# QSFP.net
KiCad netlist of a schematic drawn in Altium Designer
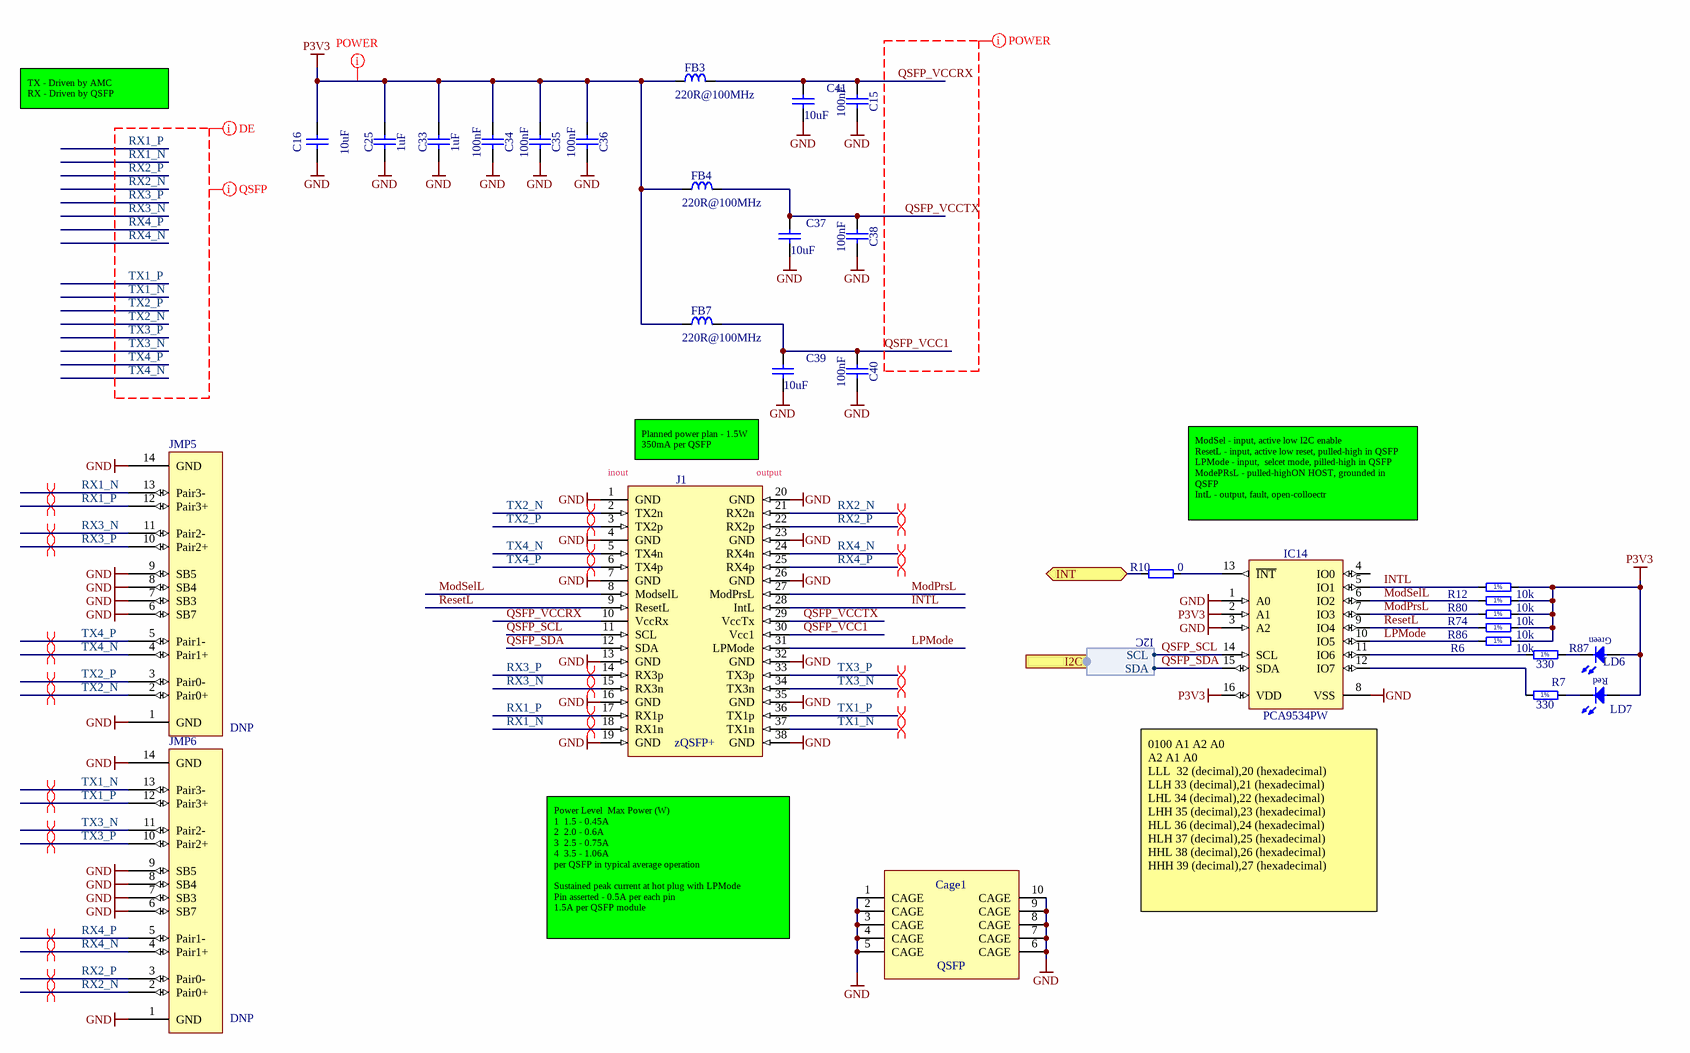
[diagram p0: QSFP.SchDoc]

(export (version "E")
  (design (tool "Eeschema 10.0.6"))
  (components
    (comp (ref "C15")
      (value "100nF")
      (footprint "CAPC0603X33N")
      (description "Non-polarised capacitor")
      (fields
        (field (name "PART NUMBER") "CC0201_100NF_6.3V_10%_X5R")
        (field (name "VOLTAGE") "6.3V")
        (field (name "AUTHOR") "CERN DEM JLC")
      )
      (libsource (lib "Capacitors") (part "Capacitor - non polarized"))
    )
    (comp (ref "C16")
      (value "10uF")
      (footprint "CAPC2012X135N")
      (description "Non-polarised capacitor")
      (fields
        (field (name "PART NUMBER") "CC0805_10UF_10V_10%_X7R")
        (field (name "VOLTAGE") "10V")
        (field (name "AUTHOR") "CERN DEM JLC")
      )
      (libsource (lib "Capacitors") (part "Capacitor - non polarized"))
    )
    (comp (ref "C25")
      (value "1uF")
      (footprint "CAPC1608X87N")
      (description "Non-polarised capacitor")
      (fields
        (field (name "PART NUMBER") "CC0603_1UF_25V_10%_X7R")
        (field (name "VOLTAGE") "25V")
        (field (name "AUTHOR") "CERN DEM JLC")
      )
      (libsource (lib "Capacitors") (part "Capacitor - non polarized"))
    )
    (comp (ref "C33")
      (value "1uF")
      (footprint "CAPC1608X87N")
      (description "Non-polarised capacitor")
      (fields
        (field (name "PART NUMBER") "CC0603_1UF_25V_10%_X7R")
        (field (name "VOLTAGE") "25V")
        (field (name "AUTHOR") "CERN DEM JLC")
      )
      (libsource (lib "Capacitors") (part "Capacitor - non polarized"))
    )
    (comp (ref "C34")
      (value "100nF")
      (footprint "CAPC0603X33N")
      (description "Non-polarised capacitor")
      (fields
        (field (name "PART NUMBER") "CC0201_100NF_6.3V_10%_X5R")
        (field (name "VOLTAGE") "6.3V")
        (field (name "AUTHOR") "CERN DEM JLC")
      )
      (libsource (lib "Capacitors") (part "Capacitor - non polarized"))
    )
    (comp (ref "C35")
      (value "100nF")
      (footprint "CAPC0603X33N")
      (description "Non-polarised capacitor")
      (fields
        (field (name "PART NUMBER") "CC0201_100NF_6.3V_10%_X5R")
        (field (name "VOLTAGE") "6.3V")
        (field (name "AUTHOR") "CERN DEM JLC")
      )
      (libsource (lib "Capacitors") (part "Capacitor - non polarized"))
    )
    (comp (ref "C36")
      (value "100nF")
      (footprint "CAPC0603X33N")
      (description "Non-polarised capacitor")
      (fields
        (field (name "PART NUMBER") "CC0201_100NF_6.3V_10%_X5R")
        (field (name "VOLTAGE") "6.3V")
        (field (name "AUTHOR") "CERN DEM JLC")
      )
      (libsource (lib "Capacitors") (part "Capacitor - non polarized"))
    )
    (comp (ref "C37")
      (value "10uF")
      (footprint "CAPC2012X135N")
      (description "Non-polarised capacitor")
      (fields
        (field (name "PART NUMBER") "CC0805_10UF_10V_10%_X7R")
        (field (name "VOLTAGE") "10V")
        (field (name "AUTHOR") "CERN DEM JLC")
      )
      (libsource (lib "Capacitors") (part "Capacitor - non polarized"))
    )
    (comp (ref "C38")
      (value "100nF")
      (footprint "CAPC0603X33N")
      (description "Non-polarised capacitor")
      (fields
        (field (name "PART NUMBER") "CC0201_100NF_6.3V_10%_X5R")
        (field (name "VOLTAGE") "6.3V")
        (field (name "AUTHOR") "CERN DEM JLC")
      )
      (libsource (lib "Capacitors") (part "Capacitor - non polarized"))
    )
    (comp (ref "C39")
      (value "10uF")
      (footprint "CAPC2012X135N")
      (description "Non-polarised capacitor")
      (fields
        (field (name "PART NUMBER") "CC0805_10UF_10V_10%_X7R")
        (field (name "VOLTAGE") "10V")
        (field (name "AUTHOR") "CERN DEM JLC")
      )
      (libsource (lib "Capacitors") (part "Capacitor - non polarized"))
    )
    (comp (ref "C40")
      (value "100nF")
      (footprint "CAPC0603X33N")
      (description "Non-polarised capacitor")
      (fields
        (field (name "PART NUMBER") "CC0201_100NF_6.3V_10%_X5R")
        (field (name "VOLTAGE") "6.3V")
        (field (name "AUTHOR") "CERN DEM JLC")
      )
      (libsource (lib "Capacitors") (part "Capacitor - non polarized"))
    )
    (comp (ref "C41")
      (value "10uF")
      (footprint "CAPC2012X135N")
      (description "Non-polarised capacitor")
      (fields
        (field (name "PART NUMBER") "CC0805_10UF_10V_10%_X7R")
        (field (name "VOLTAGE") "10V")
        (field (name "AUTHOR") "CERN DEM JLC")
      )
      (libsource (lib "Capacitors") (part "Capacitor - non polarized"))
    )
    (comp (ref "Cage1")
      (value "QSFP")
      (footprint "TYCO_2170703-7")
      (description "QSFP 1x1 Cage (10Pins)")
      (fields
        (field (name "PART NUMBER") "TYCO_2170703-7")
        (field (name "MANUFACTURER") "TYCO ELECTRONICS")
        (field (name "AUTHOR") "CERN DEM HF")
      )
      (libsource (lib "Connectors") (part "QSFP 1x1 Cage (10Pins)"))
    )
    (comp (ref "FB3")
      (value "220R@100MHz")
      (footprint "INDC2012X105N")
      (description "Inductor")
      (fields
        (field (name "PART NUMBER") "IND0805_MURATA_BLM21PG221SN1D")
        (field (name "POWER") "2A")
        (field (name "AUTHOR") "CERN DEM JLC")
      )
      (libsource (lib "Inductors & Transformers") (part "Inductor"))
    )
    (comp (ref "FB4")
      (value "220R@100MHz")
      (footprint "INDC2012X105N")
      (description "Inductor")
      (fields
        (field (name "PART NUMBER") "IND0805_MURATA_BLM21PG221SN1D")
        (field (name "POWER") "2A")
        (field (name "AUTHOR") "CERN DEM JLC")
      )
      (libsource (lib "Inductors & Transformers") (part "Inductor"))
    )
    (comp (ref "FB7")
      (value "220R@100MHz")
      (footprint "INDC2012X105N")
      (description "Inductor")
      (fields
        (field (name "PART NUMBER") "IND0805_MURATA_BLM21PG221SN1D")
        (field (name "POWER") "2A")
        (field (name "AUTHOR") "CERN DEM JLC")
      )
      (libsource (lib "Inductors & Transformers") (part "Inductor"))
    )
    (comp (ref "IC14")
      (value "PCA9534PW")
      (footprint "SOP65P640X110-16N")
      (description "8-Bit I2C-Bus and SMBus Low Power I/O Port with Interrupt")
      (fields (field (name "MANUFACTURER") "ANALOG DEVICES") (field (name "AUTHOR") "CERN DEM JLC"))
      (libsource (lib "ICs And Semiconductors") (part "PCA9534PW"))
    )
    (comp (ref "J1")
      (value "zQSFP+")
      (footprint "TYCO_1551920-2")
      (description "38Position QSFP Connector  (Quad Small Form-factor Pluggable)")
      (fields
        (field (name "PART NUMBER") "TYCO_1551920-2")
        (field (name "MANUFACTURER") "TYCO ELECTRONICS")
        (field (name "AUTHOR") "CERN DEM JLC")
      )
      (libsource (lib "Connectors") (part "QSFP+x1"))
    )
    (comp (ref "JMP5")
      (value "DNP")
      (footprint "3M_Twinax_SL8801/12-10DA5-00")
      (libsource (lib "LIBRARY_SCH") (part "DNP"))
    )
    (comp (ref "JMP6")
      (value "DNP")
      (footprint "3M_Twinax_SL8801/12-10DA5-00")
      (libsource (lib "LIBRARY_SCH") (part "DNP"))
    )
    (comp (ref "LD6")
      (value "LED_AVAGO_HSME-C120")
      (footprint "LED_AVAGO_HSME-C120")
      (description "LED Green 1C 2A")
      (fields
        (field (name "MANUFACTURER") "AVAGO TECHNOLOGIES")
        (field (name "MANUFACTURER PART NUMBER") "HSME-C120")
        (field (name "AUTHOR") "CERN DEM JMW")
      )
      (libsource (lib "ICs And Semiconductors") (part "LED Green 1C 2A"))
    )
    (comp (ref "LD7")
      (value "Red")
      (footprint "LED_AVAGO_HSME-C120rev")
      (description "LED Red Avago C120")
      (fields
        (field (name "PART NUMBER") "LED_AVAGO_HSMC-C120")
        (field (name "MANUFACTURER") "AVAGO TECHNOLOGIES")
        (field (name "AUTHOR") "CERN DEM JMW")
      )
      (libsource (lib "LIBRARY_SCH") (part "LED_SMD_90deg_mini_R"))
    )
    (comp (ref "R6")
      (value "10k")
      (footprint "RESC1005X40N")
      (description "Resistor - 1%")
      (fields
        (field (name "PART NUMBER") "R0402_10K_1%_0.0625W_100PPM")
        (field (name "POWER") "0.0625W")
        (field (name "AUTHOR") "CERN DEM JLC")
      )
      (libsource (lib "Resistors") (part "Resistor - 1%"))
    )
    (comp (ref "R7")
      (value "330")
      (footprint "RESC1608X55N")
      (description "Resistor - 1%")
      (fields
        (field (name "PART NUMBER") "R0603_330R_1%_0.1W_100PPM")
        (field (name "POWER") "0.1W")
        (field (name "AUTHOR") "CERN DEM JLC")
      )
      (libsource (lib "Resistors") (part "Resistor - 1%"))
    )
    (comp (ref "R10")
      (value "0")
      (footprint "RESC1005X40N")
      (description "Resistor")
      (fields
        (field (name "PART NUMBER") "R0402_0R_JUMPER")
        (field (name "MANUFACTURER") "GENERIC")
        (field (name "AUTHOR") "CERN DEM JLC")
      )
      (libsource (lib "Resistors") (part "Resistor"))
    )
    (comp (ref "R12")
      (value "10k")
      (footprint "RESC1005X40N")
      (description "Resistor - 1%")
      (fields
        (field (name "PART NUMBER") "R0402_10K_1%_0.0625W_100PPM")
        (field (name "POWER") "0.0625W")
        (field (name "AUTHOR") "CERN DEM JLC")
      )
      (libsource (lib "Resistors") (part "Resistor - 1%"))
    )
    (comp (ref "R74")
      (value "10k")
      (footprint "RESC1005X40N")
      (description "Resistor - 1%")
      (fields
        (field (name "PART NUMBER") "R0402_10K_1%_0.0625W_100PPM")
        (field (name "POWER") "0.0625W")
        (field (name "AUTHOR") "CERN DEM JLC")
      )
      (libsource (lib "Resistors") (part "Resistor - 1%"))
    )
    (comp (ref "R80")
      (value "10k")
      (footprint "RESC1005X40N")
      (description "Resistor - 1%")
      (fields
        (field (name "PART NUMBER") "R0402_10K_1%_0.0625W_100PPM")
        (field (name "POWER") "0.0625W")
        (field (name "AUTHOR") "CERN DEM JLC")
      )
      (libsource (lib "Resistors") (part "Resistor - 1%"))
    )
    (comp (ref "R86")
      (value "10k")
      (footprint "RESC1005X40N")
      (description "Resistor - 1%")
      (fields
        (field (name "PART NUMBER") "R0402_10K_1%_0.0625W_100PPM")
        (field (name "POWER") "0.0625W")
        (field (name "AUTHOR") "CERN DEM JLC")
      )
      (libsource (lib "Resistors") (part "Resistor - 1%"))
    )
    (comp (ref "R87")
      (value "330")
      (footprint "RESC1608X55N")
      (description "Resistor - 1%")
      (fields
        (field (name "PART NUMBER") "R0603_330R_1%_0.1W_100PPM")
        (field (name "POWER") "0.1W")
        (field (name "AUTHOR") "CERN DEM JLC")
      )
      (libsource (lib "Resistors") (part "Resistor - 1%"))
    )
  )
  (nets
    (net (code "2") (name "/INT") (class "Default")
      (node (ref "R10") (pin "1") (pinfunction "1_1") (pintype "passive"))
    )
    (net (code "3") (name "/INTL") (class "Default")
      (node (ref "IC14") (pin "5") (pinfunction "IO1_5") (pintype "bidirectional"))
      (node (ref "J1") (pin "28") (pinfunction "IntL_28") (pintype "input"))
      (node (ref "R12") (pin "1") (pinfunction "1_1") (pintype "passive"))
    )
    (net (code "4") (name "/LPMode") (class "Default")
      (node (ref "IC14") (pin "10") (pinfunction "IO5_10") (pintype "bidirectional"))
      (node (ref "J1") (pin "31") (pinfunction "LPMode_31") (pintype "input"))
      (node (ref "R6") (pin "1") (pinfunction "1_1") (pintype "passive"))
    )
    (net (code "5") (name "/ModPrsL") (class "Default")
      (node (ref "IC14") (pin "7") (pinfunction "IO3_7") (pintype "bidirectional"))
      (node (ref "J1") (pin "27") (pinfunction "ModPrsL_27") (pintype "input"))
      (node (ref "R74") (pin "1") (pinfunction "1_1") (pintype "passive"))
    )
    (net (code "6") (name "/ModSelL") (class "Default")
      (node (ref "IC14") (pin "6") (pinfunction "IO2_6") (pintype "bidirectional"))
      (node (ref "J1") (pin "8") (pinfunction "ModselL_8") (pintype "input"))
      (node (ref "R80") (pin "1") (pinfunction "1_1") (pintype "passive"))
    )
    (net (code "7") (name "/QSFP_SCL") (class "Default")
      (node (ref "IC14") (pin "14") (pinfunction "SCL_14") (pintype "input"))
      (node (ref "J1") (pin "11") (pinfunction "SCL_11") (pintype "input"))
    )
    (net (code "8") (name "/QSFP_SDA") (class "Default")
      (node (ref "IC14") (pin "15") (pinfunction "SDA_15") (pintype "bidirectional"))
      (node (ref "J1") (pin "12") (pinfunction "SDA_12") (pintype "input"))
    )
    (net (code "9") (name "/QSFP_VCC1") (class "Default")
      (node (ref "C39") (pin "1") (pinfunction "1_1") (pintype "passive"))
      (node (ref "C40") (pin "1") (pinfunction "1_1") (pintype "passive"))
      (node (ref "FB7") (pin "2") (pinfunction "2_2") (pintype "passive"))
      (node (ref "J1") (pin "30") (pinfunction "Vcc1_30") (pintype "input"))
    )
    (net (code "10") (name "/QSFP_VCCRX") (class "Default")
      (node (ref "C15") (pin "1") (pinfunction "1_1") (pintype "passive"))
      (node (ref "C41") (pin "1") (pinfunction "1_1") (pintype "passive"))
      (node (ref "FB3") (pin "2") (pinfunction "2_2") (pintype "passive"))
      (node (ref "J1") (pin "10") (pinfunction "VccRx_10") (pintype "power_in"))
    )
    (net (code "11") (name "/QSFP_VCCTX") (class "Default")
      (node (ref "C37") (pin "1") (pinfunction "1_1") (pintype "passive"))
      (node (ref "C38") (pin "1") (pinfunction "1_1") (pintype "passive"))
      (node (ref "FB4") (pin "2") (pinfunction "2_2") (pintype "passive"))
      (node (ref "J1") (pin "29") (pinfunction "VccTx_29") (pintype "input"))
    )
    (net (code "12") (name "/RX1_N") (class "Default")
      (node (ref "J1") (pin "18") (pinfunction "RX1n_18") (pintype "input"))
      (node (ref "JMP5") (pin "13") (pinfunction "Pair3-_13") (pintype "bidirectional"))
    )
    (net (code "13") (name "/RX1_P") (class "Default")
      (node (ref "J1") (pin "17") (pinfunction "RX1p_17") (pintype "input"))
      (node (ref "JMP5") (pin "12") (pinfunction "Pair3+_12") (pintype "bidirectional"))
    )
    (net (code "14") (name "/RX2_N") (class "Default")
      (node (ref "J1") (pin "21") (pinfunction "RX2n_21") (pintype "input"))
      (node (ref "JMP6") (pin "2") (pinfunction "Pair0+_2") (pintype "bidirectional"))
    )
    (net (code "15") (name "/RX2_P") (class "Default")
      (node (ref "J1") (pin "22") (pinfunction "RX2p_22") (pintype "input"))
      (node (ref "JMP6") (pin "3") (pinfunction "Pair0-_3") (pintype "bidirectional"))
    )
    (net (code "16") (name "/RX3_N") (class "Default")
      (node (ref "J1") (pin "15") (pinfunction "RX3n_15") (pintype "input"))
      (node (ref "JMP5") (pin "11") (pinfunction "Pair2-_11") (pintype "bidirectional"))
    )
    (net (code "17") (name "/RX3_P") (class "Default")
      (node (ref "J1") (pin "14") (pinfunction "RX3p_14") (pintype "input"))
      (node (ref "JMP5") (pin "10") (pinfunction "Pair2+_10") (pintype "bidirectional"))
    )
    (net (code "18") (name "/RX4_N") (class "Default")
      (node (ref "J1") (pin "24") (pinfunction "RX4n_24") (pintype "input"))
      (node (ref "JMP6") (pin "4") (pinfunction "Pair1+_4") (pintype "bidirectional"))
    )
    (net (code "19") (name "/RX4_P") (class "Default")
      (node (ref "J1") (pin "25") (pinfunction "RX4p_25") (pintype "input"))
      (node (ref "JMP6") (pin "5") (pinfunction "Pair1-_5") (pintype "bidirectional"))
    )
    (net (code "20") (name "/ResetL") (class "Default")
      (node (ref "IC14") (pin "9") (pinfunction "IO4_9") (pintype "bidirectional"))
      (node (ref "J1") (pin "9") (pinfunction "ResetL_9") (pintype "input"))
      (node (ref "R86") (pin "1") (pinfunction "1_1") (pintype "passive"))
    )
    (net (code "21") (name "/TX1_N") (class "Default")
      (node (ref "J1") (pin "37") (pinfunction "TX1n_37") (pintype "input"))
      (node (ref "JMP6") (pin "13") (pinfunction "Pair3-_13") (pintype "bidirectional"))
    )
    (net (code "22") (name "/TX1_P") (class "Default")
      (node (ref "J1") (pin "36") (pinfunction "TX1p_36") (pintype "input"))
      (node (ref "JMP6") (pin "12") (pinfunction "Pair3+_12") (pintype "bidirectional"))
    )
    (net (code "23") (name "/TX2_N") (class "Default")
      (node (ref "J1") (pin "2") (pinfunction "TX2n_2") (pintype "input"))
      (node (ref "JMP5") (pin "2") (pinfunction "Pair0+_2") (pintype "bidirectional"))
    )
    (net (code "24") (name "/TX2_P") (class "Default")
      (node (ref "J1") (pin "3") (pinfunction "TX2p_3") (pintype "input"))
      (node (ref "JMP5") (pin "3") (pinfunction "Pair0-_3") (pintype "bidirectional"))
    )
    (net (code "25") (name "/TX3_N") (class "Default")
      (node (ref "J1") (pin "34") (pinfunction "TX3n_34") (pintype "input"))
      (node (ref "JMP6") (pin "11") (pinfunction "Pair2-_11") (pintype "bidirectional"))
    )
    (net (code "26") (name "/TX3_P") (class "Default")
      (node (ref "J1") (pin "33") (pinfunction "TX3p_33") (pintype "input"))
      (node (ref "JMP6") (pin "10") (pinfunction "Pair2+_10") (pintype "bidirectional"))
    )
    (net (code "27") (name "/TX4_N") (class "Default")
      (node (ref "J1") (pin "5") (pinfunction "TX4n_5") (pintype "input"))
      (node (ref "JMP5") (pin "4") (pinfunction "Pair1+_4") (pintype "bidirectional"))
    )
    (net (code "28") (name "/TX4_P") (class "Default")
      (node (ref "J1") (pin "6") (pinfunction "TX4p_6") (pintype "input"))
      (node (ref "JMP5") (pin "5") (pinfunction "Pair1-_5") (pintype "bidirectional"))
    )
    (net (code "30") (name "GND") (class "Default")
      (node (ref "C15") (pin "2") (pinfunction "2_2") (pintype "passive"))
      (node (ref "C16") (pin "2") (pinfunction "2_2") (pintype "passive"))
      (node (ref "C25") (pin "1") (pinfunction "1_1") (pintype "passive"))
      (node (ref "C33") (pin "1") (pinfunction "1_1") (pintype "passive"))
      (node (ref "C34") (pin "2") (pinfunction "2_2") (pintype "passive"))
      (node (ref "C35") (pin "2") (pinfunction "2_2") (pintype "passive"))
      (node (ref "C36") (pin "2") (pinfunction "2_2") (pintype "passive"))
      (node (ref "C37") (pin "2") (pinfunction "2_2") (pintype "passive"))
      (node (ref "C38") (pin "2") (pinfunction "2_2") (pintype "passive"))
      (node (ref "C39") (pin "2") (pinfunction "2_2") (pintype "passive"))
      (node (ref "C40") (pin "2") (pinfunction "2_2") (pintype "passive"))
      (node (ref "C41") (pin "2") (pinfunction "2_2") (pintype "passive"))
      (node (ref "Cage1") (pin "1") (pinfunction "CAGE_1") (pintype "power_in"))
      (node (ref "Cage1") (pin "10") (pinfunction "CAGE_10") (pintype "power_in"))
      (node (ref "Cage1") (pin "2") (pinfunction "CAGE_2") (pintype "power_in"))
      (node (ref "Cage1") (pin "3") (pinfunction "CAGE_3") (pintype "power_in"))
      (node (ref "Cage1") (pin "4") (pinfunction "CAGE_4") (pintype "power_in"))
      (node (ref "Cage1") (pin "5") (pinfunction "CAGE_5") (pintype "power_in"))
      (node (ref "Cage1") (pin "6") (pinfunction "CAGE_6") (pintype "power_in"))
      (node (ref "Cage1") (pin "7") (pinfunction "CAGE_7") (pintype "power_in"))
      (node (ref "Cage1") (pin "8") (pinfunction "CAGE_8") (pintype "power_in"))
      (node (ref "Cage1") (pin "9") (pinfunction "CAGE_9") (pintype "power_in"))
      (node (ref "IC14") (pin "1") (pinfunction "A0_1") (pintype "input"))
      (node (ref "IC14") (pin "3") (pinfunction "A2_3") (pintype "input"))
      (node (ref "IC14") (pin "8") (pinfunction "VSS_8") (pintype "power_in"))
      (node (ref "J1") (pin "1") (pinfunction "GND_1") (pintype "power_in"))
      (node (ref "J1") (pin "13") (pinfunction "GND_13") (pintype "input"))
      (node (ref "J1") (pin "16") (pinfunction "GND_16") (pintype "input"))
      (node (ref "J1") (pin "19") (pinfunction "GND_19") (pintype "input"))
      (node (ref "J1") (pin "20") (pinfunction "GND_20") (pintype "input"))
      (node (ref "J1") (pin "23") (pinfunction "GND_23") (pintype "input"))
      (node (ref "J1") (pin "26") (pinfunction "GND_26") (pintype "input"))
      (node (ref "J1") (pin "32") (pinfunction "GND_32") (pintype "input"))
      (node (ref "J1") (pin "35") (pinfunction "GND_35") (pintype "input"))
      (node (ref "J1") (pin "38") (pinfunction "GND_38") (pintype "input"))
      (node (ref "J1") (pin "4") (pinfunction "GND_4") (pintype "power_in"))
      (node (ref "J1") (pin "7") (pinfunction "GND_7") (pintype "power_in"))
      (node (ref "JMP5") (pin "1") (pinfunction "GND_1") (pintype "power_in"))
      (node (ref "JMP5") (pin "14") (pinfunction "GND_14") (pintype "power_in"))
      (node (ref "JMP5") (pin "6") (pinfunction "SB7_6") (pintype "bidirectional"))
      (node (ref "JMP5") (pin "7") (pinfunction "SB3_7") (pintype "bidirectional"))
      (node (ref "JMP5") (pin "8") (pinfunction "SB4_8") (pintype "bidirectional"))
      (node (ref "JMP5") (pin "9") (pinfunction "SB5_9") (pintype "bidirectional"))
      (node (ref "JMP6") (pin "1") (pinfunction "GND_1") (pintype "power_in"))
      (node (ref "JMP6") (pin "14") (pinfunction "GND_14") (pintype "power_in"))
      (node (ref "JMP6") (pin "6") (pinfunction "SB7_6") (pintype "bidirectional"))
      (node (ref "JMP6") (pin "7") (pinfunction "SB3_7") (pintype "bidirectional"))
      (node (ref "JMP6") (pin "8") (pinfunction "SB4_8") (pintype "bidirectional"))
      (node (ref "JMP6") (pin "9") (pinfunction "SB5_9") (pintype "bidirectional"))
    )
    (net (code "31") (name "Net-(IC14-IO6)") (class "Default")
      (node (ref "IC14") (pin "11") (pinfunction "IO6_11") (pintype "bidirectional"))
      (node (ref "R87") (pin "1") (pinfunction "1_1") (pintype "passive"))
    )
    (net (code "32") (name "Net-(IC14-IO7)") (class "Default")
      (node (ref "IC14") (pin "12") (pinfunction "IO7_12") (pintype "bidirectional"))
      (node (ref "R7") (pin "1") (pinfunction "1_1") (pintype "passive"))
    )
    (net (code "33") (name "Net-(IC14-~{INT})") (class "Default")
      (node (ref "IC14") (pin "13") (pinfunction "~{INT}_13") (pintype "output"))
      (node (ref "R10") (pin "2") (pinfunction "2_2") (pintype "passive"))
    )
    (net (code "34") (name "Net-(LD6-C)") (class "Default")
      (node (ref "LD6") (pin "1") (pinfunction "C_1") (pintype "passive"))
      (node (ref "R87") (pin "2") (pinfunction "2_2") (pintype "passive"))
    )
    (net (code "35") (name "Net-(LD7-C)") (class "Default")
      (node (ref "LD7") (pin "2") (pinfunction "C_2") (pintype "passive"))
      (node (ref "R7") (pin "2") (pinfunction "2_2") (pintype "passive"))
    )
    (net (code "36") (name "P3V3") (class "Default")
      (node (ref "C16") (pin "1") (pinfunction "1_1") (pintype "passive"))
      (node (ref "C25") (pin "2") (pinfunction "2_2") (pintype "passive"))
      (node (ref "C33") (pin "2") (pinfunction "2_2") (pintype "passive"))
      (node (ref "C34") (pin "1") (pinfunction "1_1") (pintype "passive"))
      (node (ref "C35") (pin "1") (pinfunction "1_1") (pintype "passive"))
      (node (ref "C36") (pin "1") (pinfunction "1_1") (pintype "passive"))
      (node (ref "FB3") (pin "1") (pinfunction "1_1") (pintype "passive"))
      (node (ref "FB4") (pin "1") (pinfunction "1_1") (pintype "passive"))
      (node (ref "FB7") (pin "1") (pinfunction "1_1") (pintype "passive"))
      (node (ref "IC14") (pin "16") (pinfunction "VDD_16") (pintype "bidirectional"))
      (node (ref "IC14") (pin "2") (pinfunction "A1_2") (pintype "input"))
      (node (ref "LD6") (pin "2") (pinfunction "A_2") (pintype "passive"))
      (node (ref "LD7") (pin "1") (pinfunction "A_1") (pintype "passive"))
      (node (ref "R12") (pin "2") (pinfunction "2_2") (pintype "passive"))
      (node (ref "R6") (pin "2") (pinfunction "2_2") (pintype "passive"))
      (node (ref "R74") (pin "2") (pinfunction "2_2") (pintype "passive"))
      (node (ref "R80") (pin "2") (pinfunction "2_2") (pintype "passive"))
      (node (ref "R86") (pin "2") (pinfunction "2_2") (pintype "passive"))
    )
    (net (code "37") (name "unconnected-(IC14-IO0-Pad4)") (class "Default")
      (node (ref "IC14") (pin "4") (pinfunction "IO0_4") (pintype "bidirectional"))
    )
  )
)
